# RP2_pico.net
KiCad netlist of a schematic drawn in Altium Designer
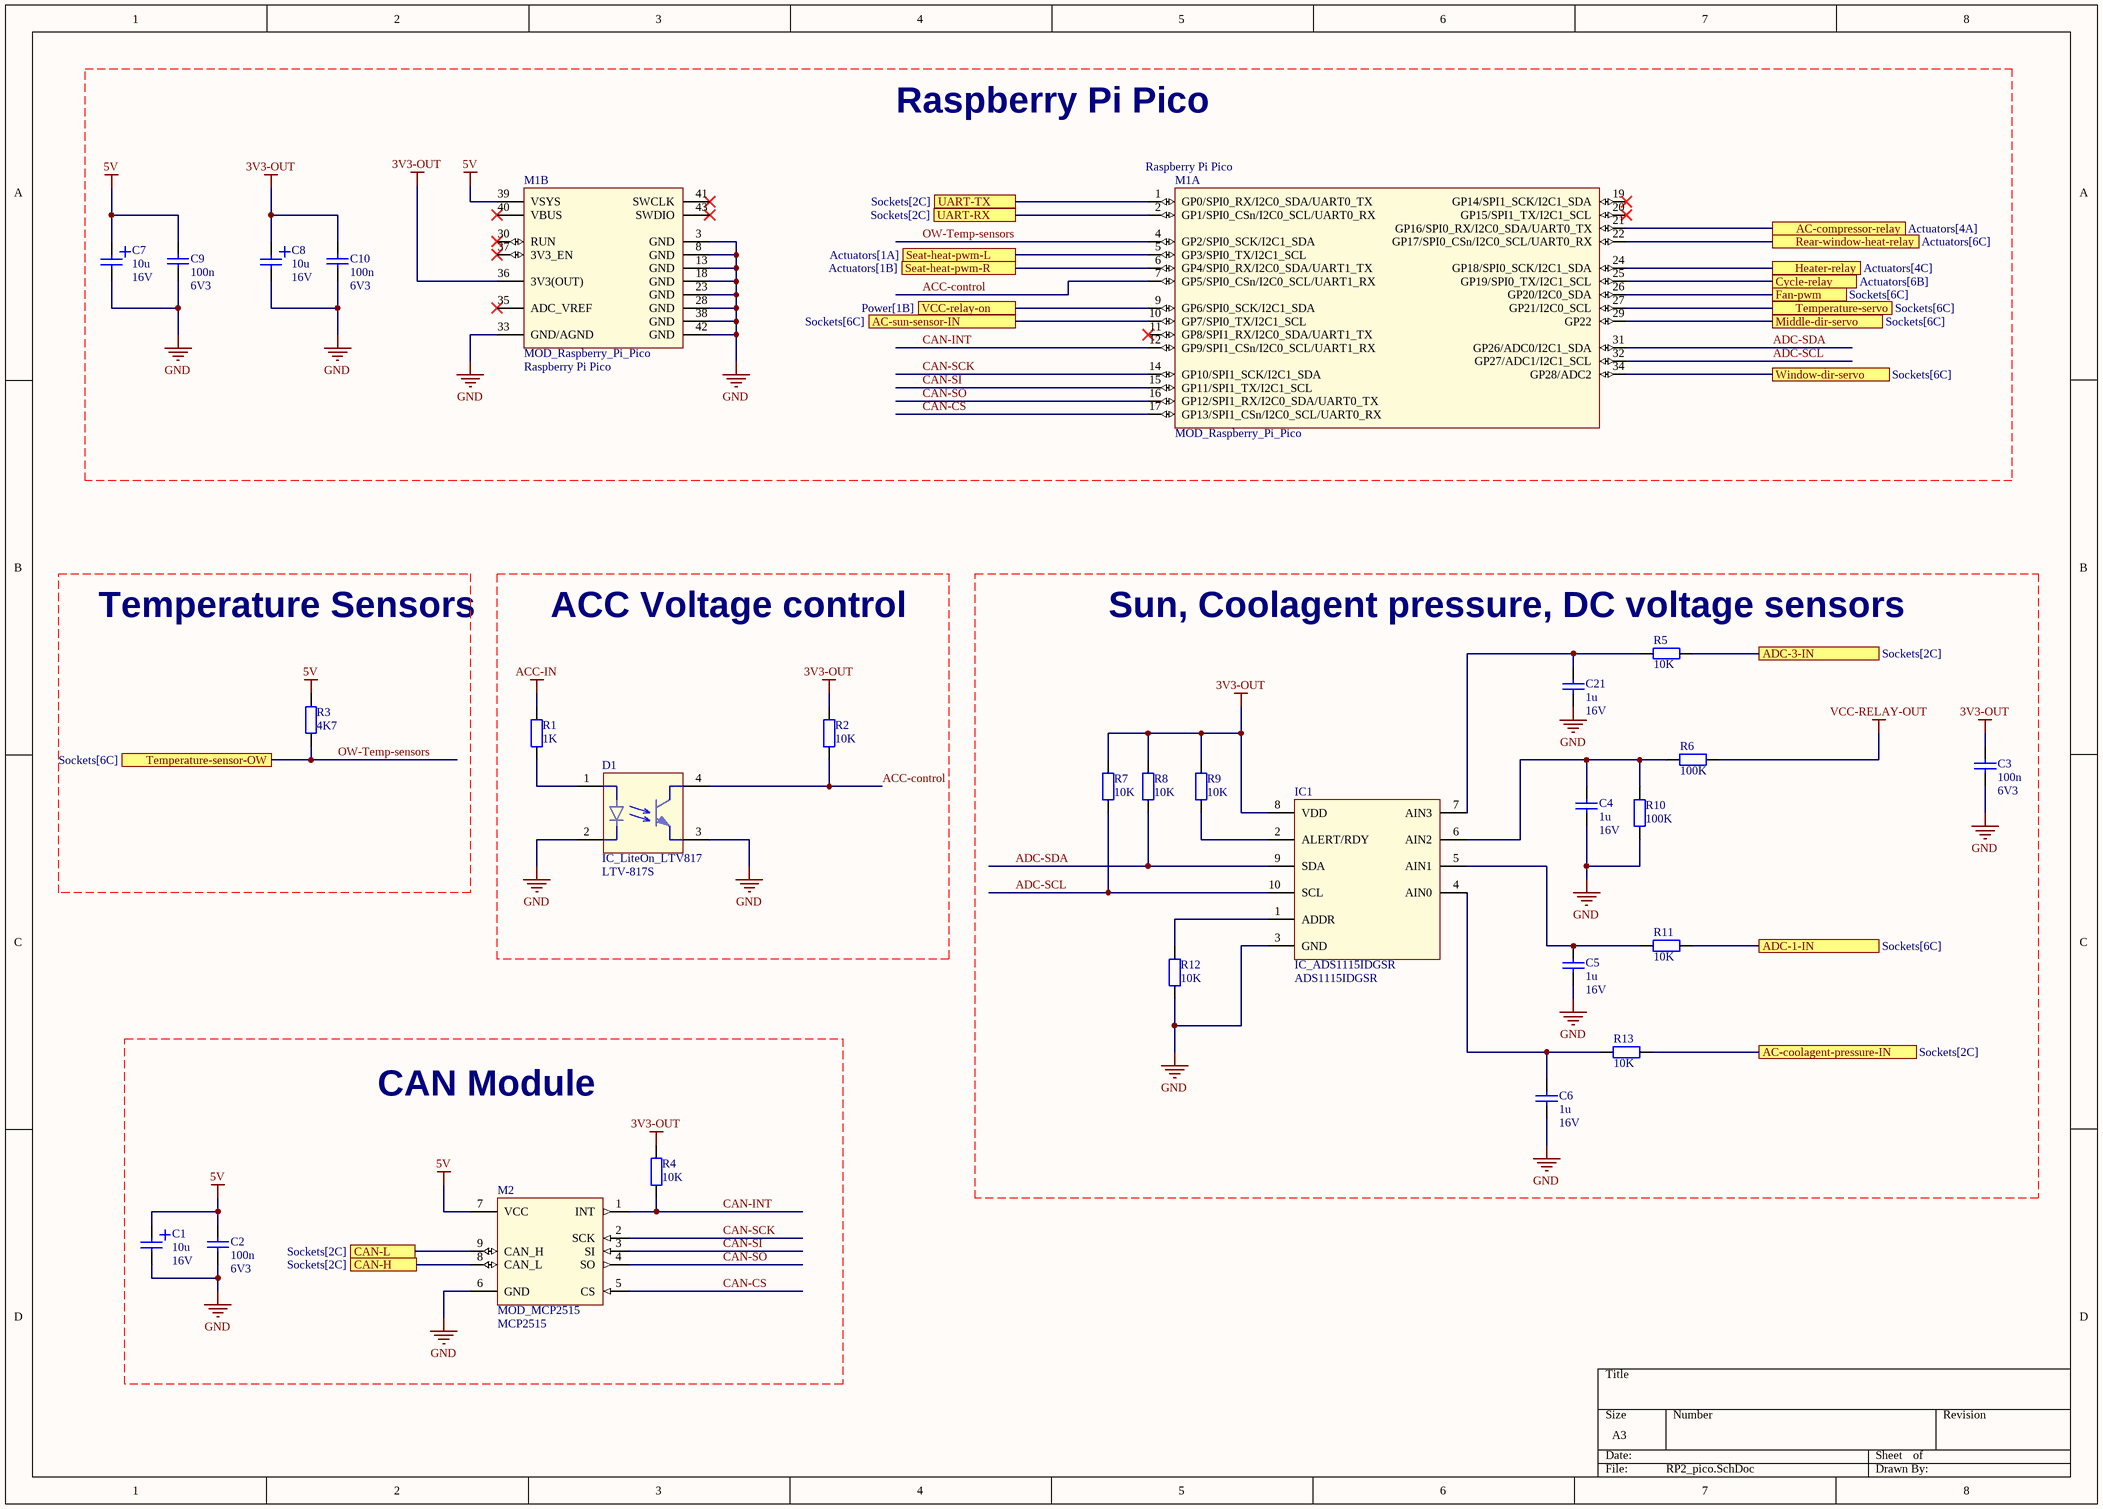
[diagram p0: RP2_pico.SchDoc]

(export (version "E")
  (design (tool "Eeschema 10.0.6"))
  (components
    (comp (ref "C1")
      (value "CAP_POL")
      (footprint "CAPAE430X550N")
      (description "ELCO 20%")
      (fields
        (field (name "VALUE1") "10u")
        (field (name "VALUE2") "16V")
        (field (name "MANUFACTURER") "Nichicon")
      )
      (libsource (lib "DSW_Lib") (part "CAP_POL"))
    )
    (comp (ref "C2")
      (value "CAP")
      (footprint "CAPC2012X88N")
      (description "X7R 10% 0805")
      (fields
        (field (name "VALUE1") "100n")
        (field (name "VALUE2") "6V3")
        (field (name "MANUFACTURER") "KEMET")
      )
      (libsource (lib "DSW_Lib") (part "CAP"))
    )
    (comp (ref "C3")
      (value "CAP")
      (footprint "CAPC2012X88N")
      (description "X7R 10% 0805")
      (fields
        (field (name "VALUE1") "100n")
        (field (name "VALUE2") "6V3")
        (field (name "MANUFACTURER") "KEMET")
      )
      (libsource (lib "DSW_Lib") (part "CAP"))
    )
    (comp (ref "C4")
      (value "CAP")
      (footprint "CAPC2012X88N")
      (fields
        (field (name "VALUE1") "1u")
        (field (name "VALUE2") "16V")
        (field (name "MANUFACTURER") "Hitano")
      )
      (libsource (lib "DSW_Lib") (part "CAP"))
    )
    (comp (ref "C5")
      (value "CAP")
      (footprint "CAPC2012X88N")
      (fields
        (field (name "VALUE1") "1u")
        (field (name "VALUE2") "16V")
        (field (name "MANUFACTURER") "Hitano")
      )
      (libsource (lib "DSW_Lib") (part "CAP"))
    )
    (comp (ref "C6")
      (value "CAP")
      (footprint "CAPC2012X88N")
      (fields
        (field (name "VALUE1") "1u")
        (field (name "VALUE2") "16V")
        (field (name "MANUFACTURER") "Hitano")
      )
      (libsource (lib "DSW_Lib") (part "CAP"))
    )
    (comp (ref "C7")
      (value "CAP_POL")
      (footprint "CAPAE430X550N")
      (description "ELCO 20%")
      (fields
        (field (name "VALUE1") "10u")
        (field (name "VALUE2") "16V")
        (field (name "MANUFACTURER") "Nichicon")
      )
      (libsource (lib "DSW_Lib") (part "CAP_POL"))
    )
    (comp (ref "C8")
      (value "CAP_POL")
      (footprint "CAPAE430X550N")
      (description "ELCO 20%")
      (fields
        (field (name "VALUE1") "10u")
        (field (name "VALUE2") "16V")
        (field (name "MANUFACTURER") "Nichicon")
      )
      (libsource (lib "DSW_Lib") (part "CAP_POL"))
    )
    (comp (ref "C9")
      (value "CAP")
      (footprint "CAPC2012X88N")
      (description "X7R 10% 0805")
      (fields
        (field (name "VALUE1") "100n")
        (field (name "VALUE2") "6V3")
        (field (name "MANUFACTURER") "KEMET")
      )
      (libsource (lib "DSW_Lib") (part "CAP"))
    )
    (comp (ref "C10")
      (value "CAP")
      (footprint "CAPC2012X88N")
      (description "X7R 10% 0805")
      (fields
        (field (name "VALUE1") "100n")
        (field (name "VALUE2") "6V3")
        (field (name "MANUFACTURER") "KEMET")
      )
      (libsource (lib "DSW_Lib") (part "CAP"))
    )
    (comp (ref "C21")
      (value "CAP")
      (footprint "CAPC2012X88N")
      (fields
        (field (name "VALUE1") "1u")
        (field (name "VALUE2") "16V")
        (field (name "MANUFACTURER") "Hitano")
      )
      (libsource (lib "DSW_Lib") (part "CAP"))
    )
    (comp (ref "D1")
      (value "IC_LiteOn_LTV817")
      (footprint "IC_LiteOn_ LTV-817S")
      (description "Transistor Output Optocouplers Optocoupler Phototrans")
      (fields (field (name "VALUE1") "LTV-817S") (field (name "MANUFACTURER") "Lite-On"))
      (libsource (lib "DSW_Lib") (part "IC_LiteOn_LTV817"))
    )
    (comp (ref "IC1")
      (value "IC_ADS1115IDGSR")
      (footprint "VSSOP-10")
      (description "Analog to Digital Converters - ADC 16B ADC w/ Int MUX PGA Comp Osc & Ref")
      (fields (field (name "VALUE1") "ADS1115IDGSR") (field (name "MANUFACTURER") "Texas Instruments"))
      (libsource (lib "DSW_Lib") (part "IC_ADS1115IDGSR"))
    )
    (comp (ref "M1")
      (value "MOD_Raspberry_Pi_Pico")
      (footprint "MOD_Raspberry_Pi_Pico")
      (description "Single Board Computers Raspberry Pi Pico")
      (fields (field (name "VALUE1") "Raspberry Pi Pico") (field (name "MANUFACTURER") "Raspberry Pi"))
      (libsource (lib "DSW_Lib") (part "MOD_Raspberry_Pi_Pico"))
    )
    (comp (ref "M2")
      (value "MOD_MCP2515")
      (footprint "MOD_MCP2515")
      (description "CAN bus  module")
      (fields (field (name "VALUE1") "MCP2515") (field (name "MANUFACTURER") "CH"))
      (libsource (lib "calibra_project") (part "12_00161"))
    )
    (comp (ref "R1")
      (value "RES")
      (footprint "RESC2012X60N")
      (description "RESISTOR, 0805, 1K, 1%, SMD")
      (fields (field (name "VALUE1") "1K") (field (name "MANUFACTURER") "Yageo"))
      (libsource (lib "") (part "RES_1"))
    )
    (comp (ref "R2")
      (value "RES")
      (footprint "RESC2012X60N")
      (description "RESISTOR, 0805, 10K, 1%, SMD")
      (fields (field (name "VALUE1") "10K") (field (name "MANUFACTURER") "Yageo"))
      (libsource (lib "") (part "RES_1"))
    )
    (comp (ref "R3")
      (value "RES")
      (footprint "RESC2012X60N")
      (description "RESISTOR, 0805, 4K7, 1%, SMD")
      (fields (field (name "VALUE1") "4K7") (field (name "MANUFACTURER") "Yageo"))
      (libsource (lib "") (part "RES_1"))
    )
    (comp (ref "R4")
      (value "RES")
      (footprint "RESC2012X60N")
      (description "RESISTOR, 0805, 10K, 1%, SMD")
      (fields (field (name "VALUE1") "10K") (field (name "MANUFACTURER") "Yageo"))
      (libsource (lib "") (part "RES_1"))
    )
    (comp (ref "R5")
      (value "RES")
      (footprint "RESC2012X60N")
      (description "RESISTOR, 0805, 100K, 1%, SMD")
      (fields (field (name "VALUE1") "10K") (field (name "MANUFACTURER") "Yageo"))
      (libsource (lib "DSW_Lib") (part "RES"))
    )
    (comp (ref "R6")
      (value "RES")
      (footprint "RESC2012X60N")
      (description "RESISTOR, 0805, 100K, 1%, SMD")
      (fields (field (name "VALUE1") "100K") (field (name "MANUFACTURER") "Yageo"))
      (libsource (lib "DSW_Lib") (part "RES"))
    )
    (comp (ref "R7")
      (value "RES")
      (footprint "RESC2012X60N")
      (description "RESISTOR, 0805, 10K, 1%, SMD")
      (fields (field (name "VALUE1") "10K") (field (name "MANUFACTURER") "Yageo"))
      (libsource (lib "") (part "RES_1"))
    )
    (comp (ref "R8")
      (value "RES")
      (footprint "RESC2012X60N")
      (description "RESISTOR, 0805, 10K, 1%, SMD")
      (fields (field (name "VALUE1") "10K") (field (name "MANUFACTURER") "Yageo"))
      (libsource (lib "") (part "RES_1"))
    )
    (comp (ref "R9")
      (value "RES")
      (footprint "RESC2012X60N")
      (description "RESISTOR, 0805, 10K, 1%, SMD")
      (fields (field (name "VALUE1") "10K") (field (name "MANUFACTURER") "Yageo"))
      (libsource (lib "") (part "RES_1"))
    )
    (comp (ref "R10")
      (value "RES")
      (footprint "RESC2012X60N")
      (description "RESISTOR, 0805, 100K, 1%, SMD")
      (fields (field (name "VALUE1") "100K") (field (name "MANUFACTURER") "Yageo"))
      (libsource (lib "") (part "RES_1"))
    )
    (comp (ref "R11")
      (value "RES")
      (footprint "RESC2012X60N")
      (description "RESISTOR, 0805, 10K, 1%, SMD")
      (fields (field (name "VALUE1") "10K") (field (name "MANUFACTURER") "Yageo"))
      (libsource (lib "DSW_Lib") (part "RES"))
    )
    (comp (ref "R12")
      (value "RES")
      (footprint "RESC2012X60N")
      (description "RESISTOR, 0805, 10K, 1%, SMD")
      (fields (field (name "VALUE1") "10K") (field (name "MANUFACTURER") "Yageo"))
      (libsource (lib "") (part "RES_1"))
    )
    (comp (ref "R13")
      (value "RES")
      (footprint "RESC2012X60N")
      (description "RESISTOR, 0805, 10K, 1%, SMD")
      (fields (field (name "VALUE1") "10K") (field (name "MANUFACTURER") "Yageo"))
      (libsource (lib "DSW_Lib") (part "RES"))
    )
  )
  (nets
    (net (code "1") (name "/AC-compressor-relay") (class "Default")
      (node (ref "M1") (pin "21") (pinfunction "GP16/SPI0_RX/I2C0_SDA/UART0_TX_21") (pintype "bidirectional"))
    )
    (net (code "2") (name "/AC-coolagent-pressure-IN") (class "Default")
      (node (ref "R13") (pin "2") (pinfunction "2_2") (pintype "passive"))
    )
    (net (code "3") (name "/AC-sun-sensor-IN") (class "Default")
      (node (ref "M1") (pin "10") (pinfunction "GP7/SPI0_TX/I2C1_SCL_10") (pintype "bidirectional"))
    )
    (net (code "4") (name "/ACC-control") (class "Default")
      (node (ref "D1") (pin "4") (pinfunction "4_4") (pintype "passive"))
      (node (ref "M1") (pin "7") (pinfunction "GP5/SPI0_CSn/I2C0_SCL/UART1_RX_7") (pintype "bidirectional"))
      (node (ref "R2") (pin "1") (pinfunction "1_1") (pintype "passive"))
    )
    (net (code "5") (name "/ADC-1-IN") (class "Default")
      (node (ref "R11") (pin "2") (pinfunction "2_2") (pintype "passive"))
    )
    (net (code "6") (name "/ADC-3-IN") (class "Default")
      (node (ref "R5") (pin "2") (pinfunction "2_2") (pintype "passive"))
    )
    (net (code "7") (name "/ADC-SCL") (class "Default")
      (node (ref "IC1") (pin "10") (pinfunction "SCL_10") (pintype "passive"))
      (node (ref "M1") (pin "32") (pinfunction "GP27/ADC1/I2C1_SCL_32") (pintype "bidirectional"))
      (node (ref "R7") (pin "1") (pinfunction "1_1") (pintype "passive"))
    )
    (net (code "8") (name "/ADC-SDA") (class "Default")
      (node (ref "IC1") (pin "9") (pinfunction "SDA_9") (pintype "passive"))
      (node (ref "M1") (pin "31") (pinfunction "GP26/ADC0/I2C1_SDA_31") (pintype "bidirectional"))
      (node (ref "R8") (pin "1") (pinfunction "1_1") (pintype "passive"))
    )
    (net (code "9") (name "/CAN-CS") (class "Default")
      (node (ref "M1") (pin "17") (pinfunction "GP13/SPI1_CSn/I2C0_SCL/UART0_RX_17") (pintype "bidirectional"))
      (node (ref "M2") (pin "5") (pinfunction "CS_5") (pintype "input"))
    )
    (net (code "10") (name "/CAN-H") (class "Default")
      (node (ref "M2") (pin "8") (pinfunction "CAN_L_8") (pintype "bidirectional"))
    )
    (net (code "11") (name "/CAN-INT") (class "Default")
      (node (ref "M1") (pin "12") (pinfunction "GP9/SPI1_CSn/I2C0_SCL/UART1_RX_12") (pintype "bidirectional"))
      (node (ref "M2") (pin "1") (pinfunction "INT_1") (pintype "output"))
      (node (ref "R4") (pin "1") (pinfunction "1_1") (pintype "passive"))
    )
    (net (code "12") (name "/CAN-L") (class "Default")
      (node (ref "M2") (pin "9") (pinfunction "CAN_H_9") (pintype "bidirectional"))
    )
    (net (code "13") (name "/CAN-SCK") (class "Default")
      (node (ref "M1") (pin "14") (pinfunction "GP10/SPI1_SCK/I2C1_SDA_14") (pintype "bidirectional"))
      (node (ref "M2") (pin "2") (pinfunction "SCK_2") (pintype "input"))
    )
    (net (code "14") (name "/CAN-SI") (class "Default")
      (node (ref "M1") (pin "15") (pinfunction "GP11/SPI1_TX/I2C1_SCL_15") (pintype "bidirectional"))
      (node (ref "M2") (pin "3") (pinfunction "SI_3") (pintype "input"))
    )
    (net (code "15") (name "/CAN-SO") (class "Default")
      (node (ref "M1") (pin "16") (pinfunction "GP12/SPI1_RX/I2C0_SDA/UART0_TX_16") (pintype "bidirectional"))
      (node (ref "M2") (pin "4") (pinfunction "SO_4") (pintype "output"))
    )
    (net (code "16") (name "/Cycle-relay") (class "Default")
      (node (ref "M1") (pin "25") (pinfunction "GP19/SPI0_TX/I2C1_SCL_25") (pintype "bidirectional"))
    )
    (net (code "17") (name "/Fan-pwm") (class "Default")
      (node (ref "M1") (pin "26") (pinfunction "GP20/I2C0_SDA_26") (pintype "bidirectional"))
    )
    (net (code "18") (name "/Heater-relay") (class "Default")
      (node (ref "M1") (pin "24") (pinfunction "GP18/SPI0_SCK/I2C1_SDA_24") (pintype "bidirectional"))
    )
    (net (code "19") (name "/Middle-dir-servo") (class "Default")
      (node (ref "M1") (pin "29") (pinfunction "GP22_29") (pintype "bidirectional"))
    )
    (net (code "20") (name "/OW-Temp-sensors") (class "Default")
      (node (ref "M1") (pin "4") (pinfunction "GP2/SPI0_SCK/I2C1_SDA_4") (pintype "bidirectional"))
      (node (ref "R3") (pin "1") (pinfunction "1_1") (pintype "passive"))
    )
    (net (code "21") (name "/Rear-window-heat-relay") (class "Default")
      (node (ref "M1") (pin "22") (pinfunction "GP17/SPI0_CSn/I2C0_SCL/UART0_RX_22") (pintype "bidirectional"))
    )
    (net (code "22") (name "/Seat-heat-pwm-L") (class "Default")
      (node (ref "M1") (pin "5") (pinfunction "GP3/SPI0_TX/I2C1_SCL_5") (pintype "bidirectional"))
    )
    (net (code "23") (name "/Seat-heat-pwm-R") (class "Default")
      (node (ref "M1") (pin "6") (pinfunction "GP4/SPI0_RX/I2C0_SDA/UART1_TX_6") (pintype "bidirectional"))
    )
    (net (code "24") (name "/Temperature-servo") (class "Default")
      (node (ref "M1") (pin "27") (pinfunction "GP21/I2C0_SCL_27") (pintype "bidirectional"))
    )
    (net (code "25") (name "/UART-RX") (class "Default")
      (node (ref "M1") (pin "2") (pinfunction "GP1/SPI0_CSn/I2C0_SCL/UART0_RX_2") (pintype "bidirectional"))
    )
    (net (code "26") (name "/UART-TX") (class "Default")
      (node (ref "M1") (pin "1") (pinfunction "GP0/SPI0_RX/I2C0_SDA/UART0_TX_1") (pintype "bidirectional"))
    )
    (net (code "27") (name "/VCC-relay-on") (class "Default")
      (node (ref "M1") (pin "9") (pinfunction "GP6/SPI0_SCK/I2C1_SDA_9") (pintype "bidirectional"))
    )
    (net (code "28") (name "/Window-dir-servo") (class "Default")
      (node (ref "M1") (pin "34") (pinfunction "GP28/ADC2_34") (pintype "bidirectional"))
    )
    (net (code "29") (name "3V3-OUT") (class "Default")
      (node (ref "C10") (pin "2") (pinfunction "2_2") (pintype "passive"))
      (node (ref "C3") (pin "2") (pinfunction "2_2") (pintype "passive"))
      (node (ref "C8") (pin "1") (pinfunction "1_1") (pintype "passive"))
      (node (ref "IC1") (pin "8") (pinfunction "VDD_8") (pintype "passive"))
      (node (ref "M1") (pin "36") (pinfunction "3V3(OUT)_36") (pintype "power_in"))
      (node (ref "R2") (pin "2") (pinfunction "2_2") (pintype "passive"))
      (node (ref "R4") (pin "2") (pinfunction "2_2") (pintype "passive"))
      (node (ref "R7") (pin "2") (pinfunction "2_2") (pintype "passive"))
      (node (ref "R8") (pin "2") (pinfunction "2_2") (pintype "passive"))
      (node (ref "R9") (pin "2") (pinfunction "2_2") (pintype "passive"))
    )
    (net (code "30") (name "5V") (class "Default")
      (node (ref "C1") (pin "1") (pinfunction "1_1") (pintype "passive"))
      (node (ref "C2") (pin "2") (pinfunction "2_2") (pintype "passive"))
      (node (ref "C7") (pin "1") (pinfunction "1_1") (pintype "passive"))
      (node (ref "C9") (pin "2") (pinfunction "2_2") (pintype "passive"))
      (node (ref "M1") (pin "39") (pinfunction "VSYS_39") (pintype "power_in"))
      (node (ref "M2") (pin "7") (pinfunction "VCC_7") (pintype "power_in"))
      (node (ref "R3") (pin "2") (pinfunction "2_2") (pintype "passive"))
    )
    (net (code "31") (name "ACC-IN") (class "Default")
      (node (ref "R1") (pin "2") (pinfunction "2_2") (pintype "passive"))
    )
    (net (code "32") (name "GND") (class "Default")
      (node (ref "C1") (pin "2") (pinfunction "2_2") (pintype "passive"))
      (node (ref "C10") (pin "1") (pinfunction "1_1") (pintype "passive"))
      (node (ref "C2") (pin "1") (pinfunction "1_1") (pintype "passive"))
      (node (ref "C21") (pin "1") (pinfunction "1_1") (pintype "passive"))
      (node (ref "C3") (pin "1") (pinfunction "1_1") (pintype "passive"))
      (node (ref "C4") (pin "1") (pinfunction "1_1") (pintype "passive"))
      (node (ref "C5") (pin "1") (pinfunction "1_1") (pintype "passive"))
      (node (ref "C6") (pin "1") (pinfunction "1_1") (pintype "passive"))
      (node (ref "C7") (pin "2") (pinfunction "2_2") (pintype "passive"))
      (node (ref "C8") (pin "2") (pinfunction "2_2") (pintype "passive"))
      (node (ref "C9") (pin "1") (pinfunction "1_1") (pintype "passive"))
      (node (ref "D1") (pin "2") (pinfunction "2_2") (pintype "passive"))
      (node (ref "D1") (pin "3") (pinfunction "3_3") (pintype "passive"))
      (node (ref "IC1") (pin "3") (pinfunction "GND_3") (pintype "passive"))
      (node (ref "M1") (pin "13") (pinfunction "GND_13") (pintype "power_in"))
      (node (ref "M1") (pin "18") (pinfunction "GND_18") (pintype "power_in"))
      (node (ref "M1") (pin "23") (pinfunction "GND_23") (pintype "power_in"))
      (node (ref "M1") (pin "28") (pinfunction "GND_28") (pintype "power_in"))
      (node (ref "M1") (pin "3") (pinfunction "GND_3") (pintype "power_in"))
      (node (ref "M1") (pin "33") (pinfunction "GND/AGND_33") (pintype "power_in"))
      (node (ref "M1") (pin "38") (pinfunction "GND_38") (pintype "power_in"))
      (node (ref "M1") (pin "42") (pinfunction "GND_42") (pintype "power_in"))
      (node (ref "M1") (pin "8") (pinfunction "GND_8") (pintype "power_in"))
      (node (ref "M2") (pin "6") (pinfunction "GND_6") (pintype "power_in"))
      (node (ref "R10") (pin "1") (pinfunction "1_1") (pintype "passive"))
      (node (ref "R12") (pin "1") (pinfunction "1_1") (pintype "passive"))
    )
    (net (code "33") (name "Net-(D1-Pad1)") (class "Default")
      (node (ref "D1") (pin "1") (pinfunction "1_1") (pintype "passive"))
      (node (ref "R1") (pin "1") (pinfunction "1_1") (pintype "passive"))
    )
    (net (code "34") (name "Net-(IC1-ADDR)") (class "Default")
      (node (ref "IC1") (pin "1") (pinfunction "ADDR_1") (pintype "passive"))
      (node (ref "R12") (pin "2") (pinfunction "2_2") (pintype "passive"))
    )
    (net (code "35") (name "Net-(IC1-AIN0)") (class "Default")
      (node (ref "C6") (pin "2") (pinfunction "2_2") (pintype "passive"))
      (node (ref "IC1") (pin "4") (pinfunction "AIN0_4") (pintype "passive"))
      (node (ref "R13") (pin "1") (pinfunction "1_1") (pintype "passive"))
    )
    (net (code "36") (name "Net-(IC1-AIN1)") (class "Default")
      (node (ref "C5") (pin "2") (pinfunction "2_2") (pintype "passive"))
      (node (ref "IC1") (pin "5") (pinfunction "AIN1_5") (pintype "passive"))
      (node (ref "R11") (pin "1") (pinfunction "1_1") (pintype "passive"))
    )
    (net (code "37") (name "Net-(IC1-AIN2)") (class "Default")
      (node (ref "C4") (pin "2") (pinfunction "2_2") (pintype "passive"))
      (node (ref "IC1") (pin "6") (pinfunction "AIN2_6") (pintype "passive"))
      (node (ref "R10") (pin "2") (pinfunction "2_2") (pintype "passive"))
      (node (ref "R6") (pin "1") (pinfunction "1_1") (pintype "passive"))
    )
    (net (code "38") (name "Net-(IC1-AIN3)") (class "Default")
      (node (ref "C21") (pin "2") (pinfunction "2_2") (pintype "passive"))
      (node (ref "IC1") (pin "7") (pinfunction "AIN3_7") (pintype "passive"))
      (node (ref "R5") (pin "1") (pinfunction "1_1") (pintype "passive"))
    )
    (net (code "39") (name "Net-(IC1-ALERT{slash}RDY)") (class "Default")
      (node (ref "IC1") (pin "2") (pinfunction "ALERT/RDY_2") (pintype "passive"))
      (node (ref "R9") (pin "1") (pinfunction "1_1") (pintype "passive"))
    )
    (net (code "40") (name "VCC-RELAY-OUT") (class "Default")
      (node (ref "R6") (pin "2") (pinfunction "2_2") (pintype "passive"))
    )
    (net (code "41") (name "unconnected-(M1A-GP8{slash}SPI1_RX{slash}I2C0_SDA{slash}UART1_TX-Pad11)") (class "Default")
      (node (ref "M1") (pin "11") (pinfunction "GP8/SPI1_RX/I2C0_SDA/UART1_TX_11") (pintype "bidirectional+no_connect"))
    )
    (net (code "42") (name "unconnected-(M1A-GP14{slash}SPI1_SCK{slash}I2C1_SDA-Pad19)") (class "Default")
      (node (ref "M1") (pin "19") (pinfunction "GP14/SPI1_SCK/I2C1_SDA_19") (pintype "bidirectional+no_connect"))
    )
    (net (code "43") (name "unconnected-(M1A-GP15{slash}SPI1_TX{slash}I2C1_SCL-Pad20)") (class "Default")
      (node (ref "M1") (pin "20") (pinfunction "GP15/SPI1_TX/I2C1_SCL_20") (pintype "bidirectional+no_connect"))
    )
    (net (code "44") (name "unconnected-(M1B-3V3_EN-Pad37)") (class "Default")
      (node (ref "M1") (pin "37") (pinfunction "3V3_EN_37") (pintype "bidirectional+no_connect"))
    )
    (net (code "45") (name "unconnected-(M1B-ADC_VREF-Pad35)") (class "Default")
      (node (ref "M1") (pin "35") (pinfunction "ADC_VREF_35") (pintype "power_in+no_connect"))
    )
    (net (code "46") (name "unconnected-(M1B-RUN-Pad30)") (class "Default")
      (node (ref "M1") (pin "30") (pinfunction "RUN_30") (pintype "bidirectional+no_connect"))
    )
    (net (code "47") (name "unconnected-(M1B-SWCLK-Pad41)") (class "Default")
      (node (ref "M1") (pin "41") (pinfunction "SWCLK_41") (pintype "passive+no_connect"))
    )
    (net (code "48") (name "unconnected-(M1B-SWDIO-Pad43)") (class "Default")
      (node (ref "M1") (pin "43") (pinfunction "SWDIO_43") (pintype "passive+no_connect"))
    )
    (net (code "49") (name "unconnected-(M1B-VBUS-Pad40)") (class "Default")
      (node (ref "M1") (pin "40") (pinfunction "VBUS_40") (pintype "power_in+no_connect"))
    )
  )
)
